# OSHChip_V1_0.net
KiCad netlist of a schematic drawn in Altium Designer
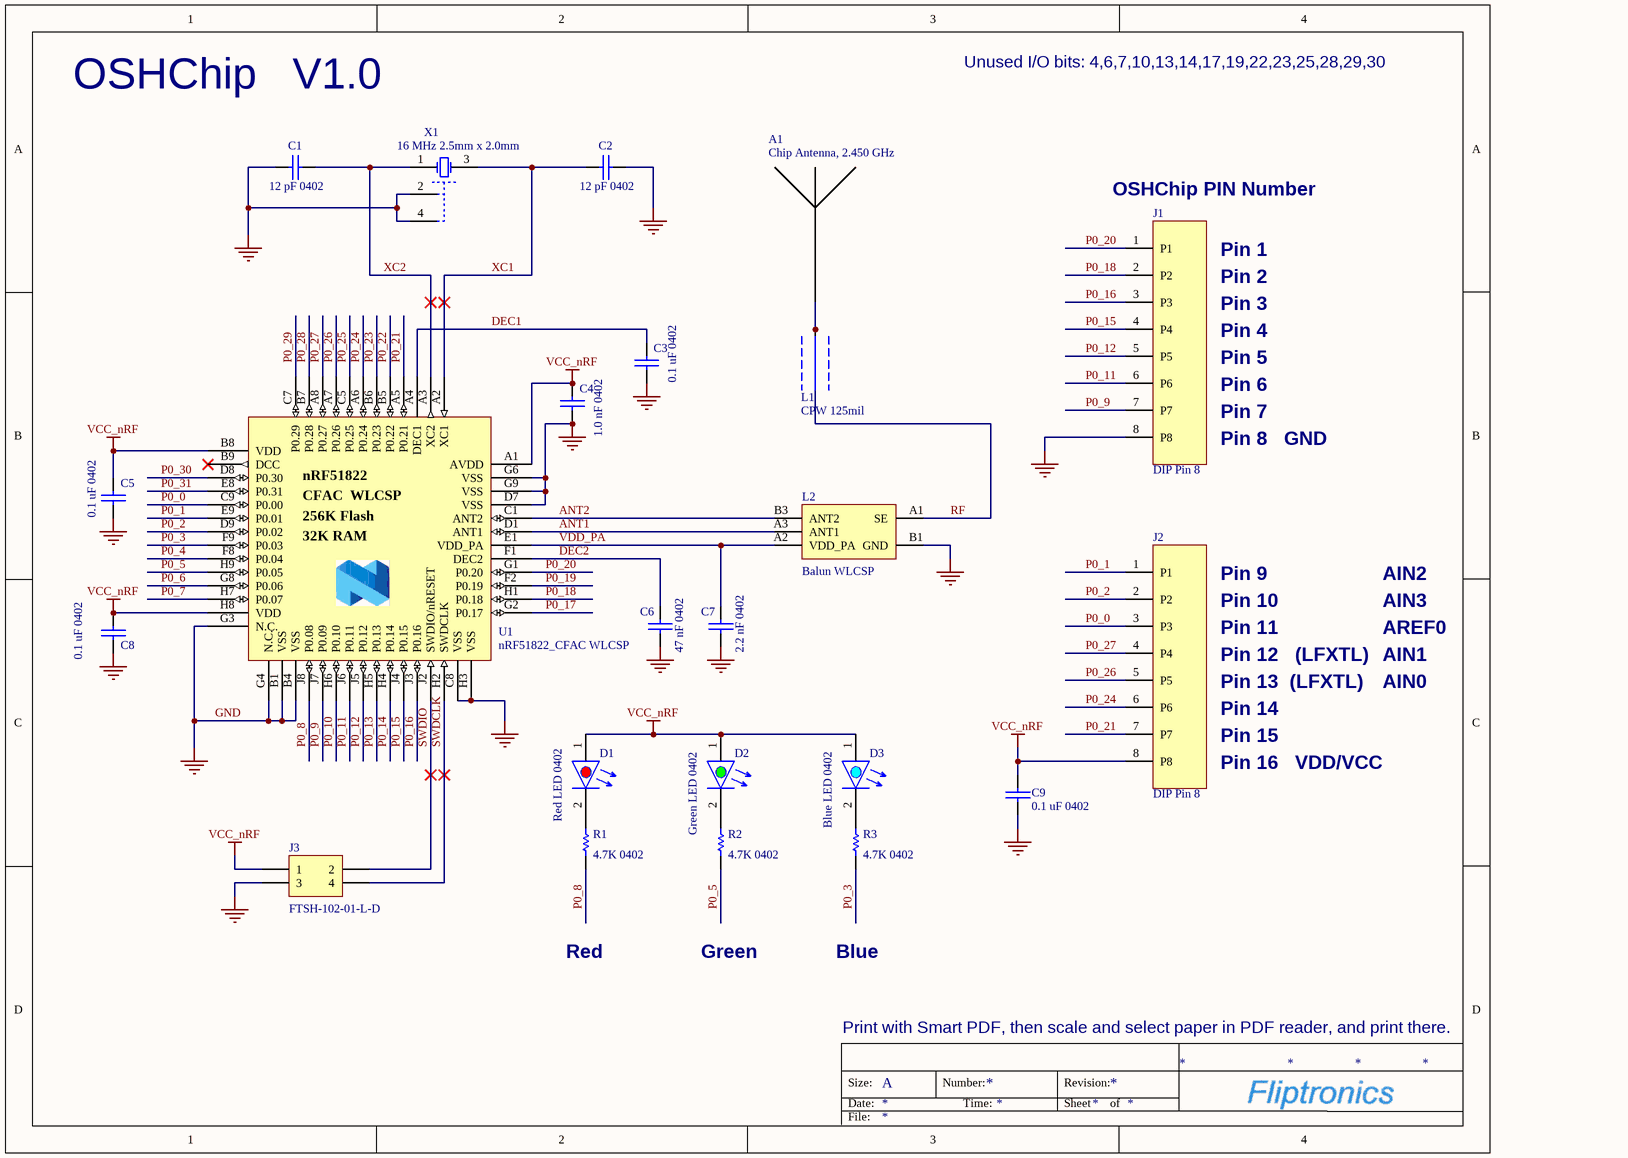
[diagram p0: OSHChip_V1.0.SchDoc]

(export (version "E")
  (design (tool "Eeschema 10.0.6"))
  (components
    (comp (ref "A1")
      (value "Chip Antenna, 2.450 GHz")
      (footprint "Footprints:AMCA31-2R450G-S1F-T")
      (description "Chip Antenna 2.4 GHz")
      (fields
        (field (name "PART NUMBER") "AMCA31-2R450G-S1F-T")
        (field (name "LATESTREVISIONNOTE") "Created by PMF")
      )
      (libsource (lib "OSHChip_V1.0") (part "A 2.4_GHZ Abracon Chip Antenna_1"))
    )
    (comp (ref "C1")
      (value "12 pF 0402")
      (footprint "Footprints:0402 CAP RouteThru")
      (description "Capacitor 12 pF 0402  50V  NP0  5%")
      (fields
        (field (name "PART NUMBER") "CL05C120JB5NNNC")
        (field (name "LATESTREVISIONNOTE") "Created by PMF")
      )
      (libsource (lib "OSHChip_V1.0") (part "C 12 pF 0402  50V  NP0  5%"))
    )
    (comp (ref "C2")
      (value "12 pF 0402")
      (footprint "Footprints:0402 CAP RouteThru")
      (description "Capacitor 12 pF 0402  50V  NP0  5%")
      (fields
        (field (name "PART NUMBER") "CL05C120JB5NNNC")
        (field (name "LATESTREVISIONNOTE") "Created by PMF")
      )
      (libsource (lib "OSHChip_V1.0") (part "C 12 pF 0402  50V  NP0  5%"))
    )
    (comp (ref "C3")
      (value "0.1 uF 0402")
      (footprint "Footprints:0402 CAP RouteThru")
      (description "Capacitor 0.1 uF 0402  10 V  X5R 10%")
      (fields
        (field (name "PART NUMBER") "CL05B104KO5NNNC")
        (field (name "LATESTREVISIONNOTE") "Created by PMF")
      )
      (libsource (lib "OSHChip_V1.0") (part "C 0.1 uF 0402  10 V  X5R 10%"))
    )
    (comp (ref "C4")
      (value "1.0 nF 0402")
      (footprint "Footprints:0402 CAP RouteThru")
      (description "Capacitor 1.0 nF 0402 25 V X7R  10%")
      (fields
        (field (name "PART NUMBER") "04025C102KAT2A")
        (field (name "LATESTREVISIONNOTE") "Created by PMF")
      )
      (libsource (lib "OSHChip_V1.0") (part "C 1.0 nF 0402 25 V X7R  10%"))
    )
    (comp (ref "C5")
      (value "0.1 uF 0402")
      (footprint "Footprints:0402 CAP RouteThru")
      (description "Capacitor 0.1 uF 0402  10 V  X5R 10%")
      (fields
        (field (name "PART NUMBER") "CL05B104KO5NNNC")
        (field (name "LATESTREVISIONNOTE") "Created by PMF")
      )
      (libsource (lib "OSHChip_V1.0") (part "C 0.1 uF 0402  10 V  X5R 10%"))
    )
    (comp (ref "C6")
      (value "47 nF 0402")
      (footprint "Footprints:0402 CAP RouteThru")
      (description "Capacitor 47 nF 0402  16V  X7R  10%")
      (fields
        (field (name "PART NUMBER") "EMK105B7473KV-F")
        (field (name "LATESTREVISIONNOTE") "Created by PMF")
      )
      (libsource (lib "OSHChip_V1.0") (part "C 47 nF 0402  16V  X7R  10%"))
    )
    (comp (ref "C7")
      (value "2.2 nF 0402")
      (footprint "Footprints:0402 CAP RouteThru")
      (description "Capacitor 2.2 nF 0402  50 V X7R  10%")
      (fields
        (field (name "PART NUMBER") "CC0402KRX7R9BB222")
        (field (name "LATESTREVISIONNOTE") "Created by PMF")
      )
      (libsource (lib "OSHChip_V1.0") (part "C 2.2 nF 0402  50 V X7R  10%"))
    )
    (comp (ref "C8")
      (value "0.1 uF 0402")
      (footprint "Footprints:0402 CAP RouteThru")
      (description "Capacitor 0.1 uF 0402  10 V  X5R 10%")
      (fields
        (field (name "PART NUMBER") "CL05B104KO5NNNC")
        (field (name "LATESTREVISIONNOTE") "Created by PMF")
      )
      (libsource (lib "OSHChip_V1.0") (part "C 0.1 uF 0402  10 V  X5R 10%"))
    )
    (comp (ref "C9")
      (value "0.1 uF 0402")
      (footprint "Footprints:0402 CAP RouteThru")
      (description "Capacitor 0.1 uF 0402  10 V  X5R 10%")
      (fields
        (field (name "PART NUMBER") "CL05B104KO5NNNC")
        (field (name "LATESTREVISIONNOTE") "Created by PMF")
      )
      (libsource (lib "OSHChip_V1.0") (part "C 0.1 uF 0402  10 V  X5R 10%"))
    )
    (comp (ref "D1")
      (value "Red LED 0402")
      (footprint "Footprints:0402 LED Route Thru RED")
      (description "LED Red 630 nm  0402")
      (fields
        (field (name "PART NUMBER") "APHHS1005SURCK")
        (field (name "LATESTREVISIONNOTE") "Created by PMF")
      )
      (libsource (lib "OSHChip_V1.0") (part "D LED APHHS1005SURCK"))
    )
    (comp (ref "D2")
      (value "Green LED 0402")
      (footprint "Footprints:0402 LED Route Thru GREEN")
      (description "LED APHHS1005CGCK Green 570nm  0402")
      (fields
        (field (name "PART NUMBER") "APHHS1005CGCK")
        (field (name "LATESTREVISIONNOTE") "Created by PMF")
      )
      (libsource (lib "OSHChip_V1.0") (part "D LED APHHS1005CGCK Green 570nm  0402"))
    )
    (comp (ref "D3")
      (value "Blue LED 0402")
      (footprint "Footprints:0402 LED Route Thru BLUE")
      (description "LED Blue 466 nm  0402")
      (fields
        (field (name "PART NUMBER") "LB QH9G-N1P2-35-1")
        (field (name "LATESTREVISIONNOTE") "Created by PMF")
      )
      (libsource (lib "OSHChip_V1.0") (part "D LED LB QH9G-N1P2-35-1"))
    )
    (comp (ref "J1")
      (value "DIP Pin 8")
      (footprint "Footprints:SIP 8    P2.54MM")
      (description "DIP Pin 8 Etched")
      (fields
        (field (name "PART NUMBER") "OSHChip_Pin_8")
        (field (name "LATESTREVISIONNOTE") "Created by PMF")
      )
      (libsource (lib "OSHChip_V1.0") (part "J DIP Pin 8 Etched"))
    )
    (comp (ref "J2")
      (value "DIP Pin 8")
      (footprint "Footprints:SIP 8    P2.54MM")
      (description "DIP Pin 8 Etched")
      (fields
        (field (name "PART NUMBER") "OSHChip_Pin_8")
        (field (name "LATESTREVISIONNOTE") "Created by PMF")
      )
      (libsource (lib "OSHChip_V1.0") (part "J DIP Pin 8 Etched"))
    )
    (comp (ref "J3")
      (value "FTSH-102-01-L-D")
      (footprint "Footprints:HDR_2x2_1.27mm-Through_Hole_SWD")
      (fields (field (name "LATESTREVISIONNOTE") "Created by PMF"))
      (libsource (lib "OSHChip_V1.0") (part "J Header 2X2 J-Link Lite"))
    )
    (comp (ref "L1")
      (value "CPW 125mil")
      (footprint "Footprints:CPW_125")
      (description "CPW 125mil , over ground plane, .062 board, 50 Ohm")
      (fields (field (name "LATESTREVISIONNOTE") "Created by PMF"))
      (libsource (lib "OSHChip_V1.0") (part "L CPW 125mil"))
    )
    (comp (ref "L2")
      (value "Balun WLCSP")
      (footprint "BAL-ST-WLCSP")
      (description "Balun matched to WLCSP nRF61822")
      (fields (field (name "PART NUMBER") "BAL-NRF02D3") (field (name "LATESTREVISIONNOTE") "Created by PMF"))
      (libsource (lib "OSHChip_V1.0") (part "L BAL-NRF02D3 nRF51822 Balun 50 ohm for 2.45GHz"))
    )
    (comp (ref "R1")
      (value "4.7K 0402")
      (footprint "0402 Res Route Thru")
      (description "Resistor 4.7K 0402 1/16 W 1%")
      (fields
        (field (name "PART NUMBER") "RC0402FR-074K7L")
        (field (name "LATESTREVISIONNOTE") "Created by PMF")
      )
      (libsource (lib "OSHChip_V1.0") (part "R 4.7K 0402 1/16 W 1%"))
    )
    (comp (ref "R2")
      (value "4.7K 0402")
      (footprint "0402 Res Route Thru")
      (description "Resistor 4.7K 0402 1/16 W 1%")
      (fields
        (field (name "PART NUMBER") "RC0402FR-074K7L")
        (field (name "LATESTREVISIONNOTE") "Created by PMF")
      )
      (libsource (lib "OSHChip_V1.0") (part "R 4.7K 0402 1/16 W 1%"))
    )
    (comp (ref "R3")
      (value "4.7K 0402")
      (footprint "0402 Res Route Thru")
      (description "Resistor 4.7K 0402 1/16 W 1%")
      (fields
        (field (name "PART NUMBER") "RC0402FR-074K7L")
        (field (name "LATESTREVISIONNOTE") "Created by PMF")
      )
      (libsource (lib "OSHChip_V1.0") (part "R 4.7K 0402 1/16 W 1%"))
    )
    (comp (ref "U1")
      (value "nRF51822_CFAC WLCSP")
      (footprint "Footprints:BGA62C40P9X9_383X383X55")
      (description "Multi-protocol Bluetooth Low Energy and 2.4GHz proprietary system-on-chip")
      (fields
        (field (name "PART NUMBER") "nRF51822_CFAC")
        (field (name "LATESTREVISIONNOTE") "Created by PMF")
      )
      (libsource (lib "OSHChip_V1.0") (part "U nRF51822_CFAC WLCSP, 256KB Flash, 32KB RAM"))
    )
    (comp (ref "X1")
      (value "16 MHz 2.5mm x 2.0mm")
      (footprint "Footprints:BT-XTAL_2520")
      (description "16MHz Xtal, 2.5mmx2.0mm, 10ppm,  8 pF")
      (fields (field (name "PART NUMBER") "FA-20H") (field (name "LATESTREVISIONNOTE") "Created by PMF"))
      (libsource (lib "OSHChip_V1.0") (part "X 16MHz Xtal, 2.5mmx2.0mm, 10ppm,  8 pF"))
    )
  )
  (nets
    (net (code "1") (name "/ANT1") (class "Default")
      (node (ref "L2") (pin "A3") (pinfunction "ANT1_A3") (pintype "passive"))
      (node (ref "U1") (pin "D1") (pinfunction "ANT1_D1") (pintype "bidirectional"))
    )
    (net (code "2") (name "/ANT2") (class "Default")
      (node (ref "L2") (pin "B3") (pinfunction "ANT2_B3") (pintype "passive"))
      (node (ref "U1") (pin "C1") (pinfunction "ANT2_C1") (pintype "bidirectional"))
    )
    (net (code "3") (name "/DEC1") (class "Default")
      (node (ref "C3") (pin "2") (pinfunction "2_2") (pintype "passive"))
      (node (ref "U1") (pin "A4") (pinfunction "DEC1_A4") (pintype "power_in"))
    )
    (net (code "4") (name "/DEC2") (class "Default")
      (node (ref "C6") (pin "2") (pinfunction "2_2") (pintype "passive"))
      (node (ref "U1") (pin "F1") (pinfunction "DEC2_F1") (pintype "power_in"))
    )
    (net (code "5") (name "/P0_0") (class "Default")
      (node (ref "J2") (pin "3") (pinfunction "P3_3") (pintype "passive"))
      (node (ref "U1") (pin "C9") (pinfunction "P0.00_C9") (pintype "bidirectional"))
    )
    (net (code "6") (name "/P0_1") (class "Default")
      (node (ref "J2") (pin "1") (pinfunction "P1_1") (pintype "passive"))
      (node (ref "U1") (pin "E9") (pinfunction "P0.01_E9") (pintype "bidirectional"))
    )
    (net (code "7") (name "/P0_2") (class "Default")
      (node (ref "J2") (pin "2") (pinfunction "P2_2") (pintype "passive"))
      (node (ref "U1") (pin "D9") (pinfunction "P0.02_D9") (pintype "bidirectional"))
    )
    (net (code "8") (name "/P0_3") (class "Default")
      (node (ref "R3") (pin "1") (pinfunction "1_1") (pintype "passive"))
      (node (ref "U1") (pin "F9") (pinfunction "P0.03_F9") (pintype "bidirectional"))
    )
    (net (code "9") (name "/P0_4") (class "Default")
      (node (ref "U1") (pin "F8") (pinfunction "P0.04_F8") (pintype "bidirectional"))
    )
    (net (code "10") (name "/P0_5") (class "Default")
      (node (ref "R2") (pin "1") (pinfunction "1_1") (pintype "passive"))
      (node (ref "U1") (pin "H9") (pinfunction "P0.05_H9") (pintype "bidirectional"))
    )
    (net (code "11") (name "/P0_6") (class "Default")
      (node (ref "U1") (pin "G8") (pinfunction "P0.06_G8") (pintype "bidirectional"))
    )
    (net (code "12") (name "/P0_7") (class "Default")
      (node (ref "U1") (pin "H7") (pinfunction "P0.07_H7") (pintype "bidirectional"))
    )
    (net (code "13") (name "/P0_8") (class "Default")
      (node (ref "R1") (pin "1") (pinfunction "1_1") (pintype "passive"))
      (node (ref "U1") (pin "J8") (pinfunction "P0.08_J8") (pintype "bidirectional"))
    )
    (net (code "14") (name "/P0_9") (class "Default")
      (node (ref "J1") (pin "7") (pinfunction "P7_7") (pintype "passive"))
      (node (ref "U1") (pin "J7") (pinfunction "P0.09_J7") (pintype "bidirectional"))
    )
    (net (code "15") (name "/P0_10") (class "Default")
      (node (ref "U1") (pin "H6") (pinfunction "P0.10_H6") (pintype "bidirectional"))
    )
    (net (code "16") (name "/P0_11") (class "Default")
      (node (ref "J1") (pin "6") (pinfunction "P6_6") (pintype "passive"))
      (node (ref "U1") (pin "J6") (pinfunction "P0.11_J6") (pintype "bidirectional"))
    )
    (net (code "17") (name "/P0_12") (class "Default")
      (node (ref "J1") (pin "5") (pinfunction "P5_5") (pintype "passive"))
      (node (ref "U1") (pin "J5") (pinfunction "P0.12_J5") (pintype "bidirectional"))
    )
    (net (code "18") (name "/P0_13") (class "Default")
      (node (ref "U1") (pin "H5") (pinfunction "P0.13_H5") (pintype "bidirectional"))
    )
    (net (code "19") (name "/P0_14") (class "Default")
      (node (ref "U1") (pin "H4") (pinfunction "P0.14_H4") (pintype "bidirectional"))
    )
    (net (code "20") (name "/P0_15") (class "Default")
      (node (ref "J1") (pin "4") (pinfunction "P4_4") (pintype "passive"))
      (node (ref "U1") (pin "J4") (pinfunction "P0.15_J4") (pintype "bidirectional"))
    )
    (net (code "21") (name "/P0_16") (class "Default")
      (node (ref "J1") (pin "3") (pinfunction "P3_3") (pintype "passive"))
      (node (ref "U1") (pin "J3") (pinfunction "P0.16_J3") (pintype "bidirectional"))
    )
    (net (code "22") (name "/P0_17") (class "Default")
      (node (ref "U1") (pin "G2") (pinfunction "P0.17_G2") (pintype "bidirectional"))
    )
    (net (code "23") (name "/P0_18") (class "Default")
      (node (ref "J1") (pin "2") (pinfunction "P2_2") (pintype "passive"))
      (node (ref "U1") (pin "H1") (pinfunction "P0.18_H1") (pintype "bidirectional"))
    )
    (net (code "24") (name "/P0_19") (class "Default")
      (node (ref "U1") (pin "F2") (pinfunction "P0.19_F2") (pintype "bidirectional"))
    )
    (net (code "25") (name "/P0_20") (class "Default")
      (node (ref "J1") (pin "1") (pinfunction "P1_1") (pintype "passive"))
      (node (ref "U1") (pin "G1") (pinfunction "P0.20_G1") (pintype "bidirectional"))
    )
    (net (code "26") (name "/P0_21") (class "Default")
      (node (ref "J2") (pin "7") (pinfunction "P7_7") (pintype "passive"))
      (node (ref "U1") (pin "A5") (pinfunction "P0.21_A5") (pintype "bidirectional"))
    )
    (net (code "27") (name "/P0_22") (class "Default")
      (node (ref "U1") (pin "B5") (pinfunction "P0.22_B5") (pintype "bidirectional"))
    )
    (net (code "28") (name "/P0_23") (class "Default")
      (node (ref "U1") (pin "B6") (pinfunction "P0.23_B6") (pintype "bidirectional"))
    )
    (net (code "29") (name "/P0_24") (class "Default")
      (node (ref "J2") (pin "6") (pinfunction "P6_6") (pintype "passive"))
      (node (ref "U1") (pin "A6") (pinfunction "P0.24_A6") (pintype "bidirectional"))
    )
    (net (code "30") (name "/P0_25") (class "Default")
      (node (ref "U1") (pin "C5") (pinfunction "P0.25_C5") (pintype "bidirectional"))
    )
    (net (code "31") (name "/P0_26") (class "Default")
      (node (ref "J2") (pin "5") (pinfunction "P5_5") (pintype "passive"))
      (node (ref "U1") (pin "A7") (pinfunction "P0.26_A7") (pintype "bidirectional"))
    )
    (net (code "32") (name "/P0_27") (class "Default")
      (node (ref "J2") (pin "4") (pinfunction "P4_4") (pintype "passive"))
      (node (ref "U1") (pin "A8") (pinfunction "P0.27_A8") (pintype "bidirectional"))
    )
    (net (code "33") (name "/P0_28") (class "Default")
      (node (ref "U1") (pin "B7") (pinfunction "P0.28_B7") (pintype "bidirectional"))
    )
    (net (code "34") (name "/P0_29") (class "Default")
      (node (ref "U1") (pin "C7") (pinfunction "P0.29_C7") (pintype "bidirectional"))
    )
    (net (code "35") (name "/P0_30") (class "Default")
      (node (ref "U1") (pin "D8") (pinfunction "P0.30_D8") (pintype "bidirectional"))
    )
    (net (code "36") (name "/P0_31") (class "Default")
      (node (ref "U1") (pin "E8") (pinfunction "P0.31_E8") (pintype "bidirectional"))
    )
    (net (code "37") (name "/RF") (class "Default")
      (node (ref "A1") (pin "1") (pinfunction "1_1") (pintype "passive"))
      (node (ref "L1") (pin "1") (pinfunction "1_1") (pintype "passive"))
      (node (ref "L2") (pin "A1") (pinfunction "SE_A1") (pintype "passive"))
    )
    (net (code "38") (name "/SWDCLK") (class "Default")
      (node (ref "J3") (pin "4") (pinfunction "4_4") (pintype "passive"))
      (node (ref "U1") (pin "H2") (pinfunction "SWDCLK_H2") (pintype "input"))
    )
    (net (code "39") (name "/SWDIO") (class "Default")
      (node (ref "J3") (pin "2") (pinfunction "2_2") (pintype "passive"))
      (node (ref "U1") (pin "J2") (pinfunction "SWDIO/nRESET_J2") (pintype "input"))
    )
    (net (code "40") (name "/VDD_PA") (class "Default")
      (node (ref "C7") (pin "2") (pinfunction "2_2") (pintype "passive"))
      (node (ref "L2") (pin "A2") (pinfunction "VDD_PA_A2") (pintype "passive"))
      (node (ref "U1") (pin "E1") (pinfunction "VDD_PA_E1") (pintype "power_in"))
    )
    (net (code "41") (name "/XC1") (class "Default")
      (node (ref "C2") (pin "1") (pinfunction "1_1") (pintype "passive"))
      (node (ref "U1") (pin "A2") (pinfunction "XC1_A2") (pintype "input"))
      (node (ref "X1") (pin "3") (pinfunction "OSC2_3") (pintype "passive"))
    )
    (net (code "42") (name "/XC2") (class "Default")
      (node (ref "C1") (pin "2") (pinfunction "2_2") (pintype "passive"))
      (node (ref "U1") (pin "A3") (pinfunction "XC2_A3") (pintype "output"))
      (node (ref "X1") (pin "1") (pinfunction "OSC1_1") (pintype "passive"))
    )
    (net (code "43") (name "GND") (class "Default")
      (node (ref "C1") (pin "1") (pinfunction "1_1") (pintype "passive"))
      (node (ref "C2") (pin "2") (pinfunction "2_2") (pintype "passive"))
      (node (ref "C3") (pin "1") (pinfunction "1_1") (pintype "passive"))
      (node (ref "C4") (pin "1") (pinfunction "1_1") (pintype "passive"))
      (node (ref "C5") (pin "1") (pinfunction "1_1") (pintype "passive"))
      (node (ref "C6") (pin "1") (pinfunction "1_1") (pintype "passive"))
      (node (ref "C7") (pin "1") (pinfunction "1_1") (pintype "passive"))
      (node (ref "C8") (pin "1") (pinfunction "1_1") (pintype "passive"))
      (node (ref "C9") (pin "1") (pinfunction "1_1") (pintype "passive"))
      (node (ref "J1") (pin "8") (pinfunction "P8_8") (pintype "passive"))
      (node (ref "J3") (pin "3") (pinfunction "3_3") (pintype "passive"))
      (node (ref "L2") (pin "B1") (pinfunction "GND_B1") (pintype "passive"))
      (node (ref "U1") (pin "B1") (pinfunction "VSS_B1") (pintype "power_in"))
      (node (ref "U1") (pin "B4") (pinfunction "VSS_B4") (pintype "power_in"))
      (node (ref "U1") (pin "C8") (pinfunction "VSS_C8") (pintype "power_in"))
      (node (ref "U1") (pin "D7") (pinfunction "VSS_D7") (pintype "power_in"))
      (node (ref "U1") (pin "G3") (pinfunction "N.C._G3") (pintype "passive"))
      (node (ref "U1") (pin "G4") (pinfunction "N.C._G4") (pintype "passive"))
      (node (ref "U1") (pin "G6") (pinfunction "VSS_G6") (pintype "power_in"))
      (node (ref "U1") (pin "G9") (pinfunction "VSS_G9") (pintype "power_in"))
      (node (ref "U1") (pin "H3") (pinfunction "VSS_H3") (pintype "power_in"))
      (node (ref "X1") (pin "2") (pinfunction "nc_2_2") (pintype "passive"))
      (node (ref "X1") (pin "4") (pinfunction "nc_4_4") (pintype "passive"))
    )
    (net (code "44") (name "Net-(D1-Pad2)") (class "Default")
      (node (ref "D1") (pin "2") (pinfunction "2_2") (pintype "passive"))
      (node (ref "R1") (pin "2") (pinfunction "2_2") (pintype "passive"))
    )
    (net (code "45") (name "Net-(D2-Pad2)") (class "Default")
      (node (ref "D2") (pin "2") (pinfunction "2_2") (pintype "passive"))
      (node (ref "R2") (pin "2") (pinfunction "2_2") (pintype "passive"))
    )
    (net (code "46") (name "Net-(D3-Pad2)") (class "Default")
      (node (ref "D3") (pin "2") (pinfunction "2_2") (pintype "passive"))
      (node (ref "R3") (pin "2") (pinfunction "2_2") (pintype "passive"))
    )
    (net (code "47") (name "VCC_nRF") (class "Default")
      (node (ref "C4") (pin "2") (pinfunction "2_2") (pintype "passive"))
      (node (ref "C5") (pin "2") (pinfunction "2_2") (pintype "passive"))
      (node (ref "C8") (pin "2") (pinfunction "2_2") (pintype "passive"))
      (node (ref "C9") (pin "2") (pinfunction "2_2") (pintype "passive"))
      (node (ref "D1") (pin "1") (pinfunction "1_1") (pintype "passive"))
      (node (ref "D2") (pin "1") (pinfunction "1_1") (pintype "passive"))
      (node (ref "D3") (pin "1") (pinfunction "1_1") (pintype "passive"))
      (node (ref "J2") (pin "8") (pinfunction "P8_8") (pintype "passive"))
      (node (ref "J3") (pin "1") (pinfunction "1_1") (pintype "passive"))
      (node (ref "U1") (pin "A1") (pinfunction "AVDD_A1") (pintype "power_in"))
      (node (ref "U1") (pin "B8") (pinfunction "VDD_B8") (pintype "power_in"))
      (node (ref "U1") (pin "H8") (pinfunction "VDD_H8") (pintype "power_in"))
    )
    (net (code "48") (name "unconnected-(U1-DCC-PadB9)") (class "Default")
      (node (ref "U1") (pin "B9") (pinfunction "DCC_B9") (pintype "output+no_connect"))
    )
  )
)
